# Sheet1.net
KiCad netlist of a schematic drawn in Altium Designer
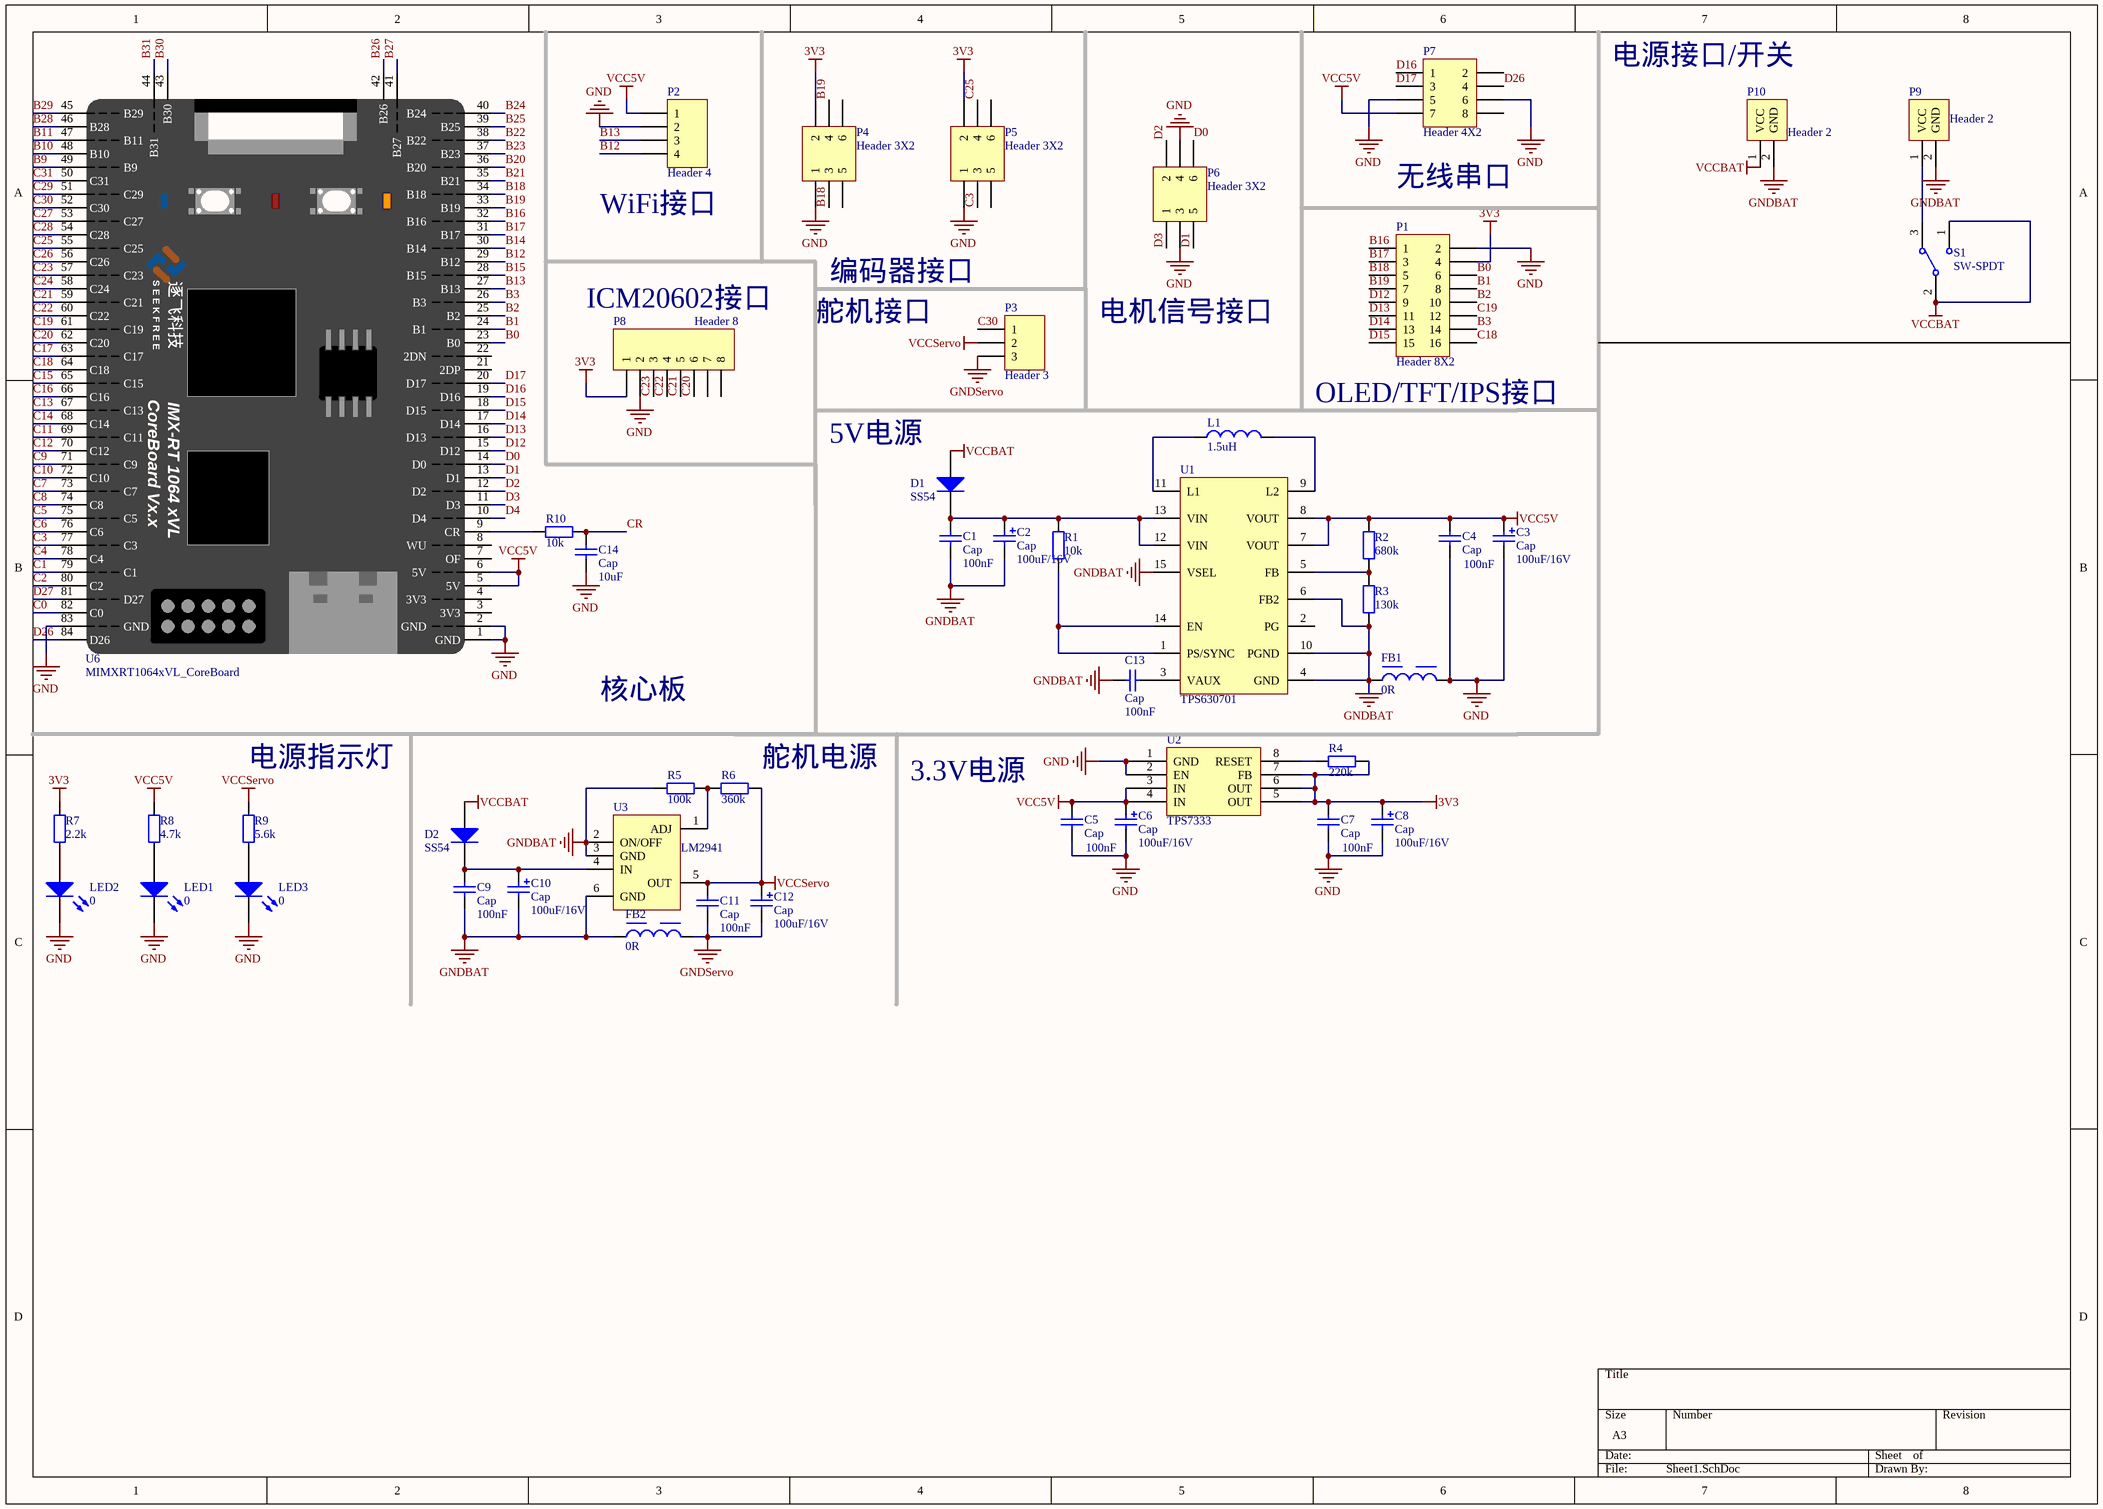
[diagram p0: Sheet1.SchDoc]

(export (version "E")
  (design (tool "Eeschema 10.0.6"))
  (components
    (comp (ref "C1")
      (value "Cap")
      (footprint "0603C")
      (description "Capacitor")
      (fields (field (name "ALTIUM_VALUE") "100nF") (field (name "PUBLISHER") "Altium Limited"))
      (libsource (lib "Schlib1") (part "Cap"))
    )
    (comp (ref "C2")
      (value "Cap")
      (description "Capacitor")
      (fields (field (name "ALTIUM_VALUE") "100uF/16V") (field (name "PUBLISHER") "Altium Limited"))
      (libsource (lib "Schlib1") (part "Cap2"))
    )
    (comp (ref "C3")
      (value "Cap")
      (description "Capacitor")
      (fields (field (name "ALTIUM_VALUE") "100uF/16V") (field (name "PUBLISHER") "Altium Limited"))
      (libsource (lib "Schlib1") (part "Cap2"))
    )
    (comp (ref "C4")
      (value "Cap")
      (footprint "0603C")
      (description "Capacitor")
      (fields (field (name "ALTIUM_VALUE") "100nF") (field (name "PUBLISHER") "Altium Limited"))
      (libsource (lib "Schlib1") (part "Cap"))
    )
    (comp (ref "C5")
      (value "Cap")
      (footprint "0603C")
      (description "Capacitor")
      (fields (field (name "ALTIUM_VALUE") "100nF") (field (name "PUBLISHER") "Altium Limited"))
      (libsource (lib "Schlib1") (part "Cap"))
    )
    (comp (ref "C6")
      (value "Cap")
      (description "Capacitor")
      (fields (field (name "ALTIUM_VALUE") "100uF/16V") (field (name "PUBLISHER") "Altium Limited"))
      (libsource (lib "Schlib1") (part "Cap2"))
    )
    (comp (ref "C7")
      (value "Cap")
      (footprint "0603C")
      (description "Capacitor")
      (fields (field (name "ALTIUM_VALUE") "100nF") (field (name "PUBLISHER") "Altium Limited"))
      (libsource (lib "Schlib1") (part "Cap"))
    )
    (comp (ref "C8")
      (value "Cap")
      (description "Capacitor")
      (fields (field (name "ALTIUM_VALUE") "100uF/16V") (field (name "PUBLISHER") "Altium Limited"))
      (libsource (lib "Schlib1") (part "Cap2"))
    )
    (comp (ref "C9")
      (value "Cap")
      (footprint "0603C")
      (description "Capacitor")
      (fields (field (name "ALTIUM_VALUE") "100nF") (field (name "PUBLISHER") "Altium Limited"))
      (libsource (lib "Schlib1") (part "Cap"))
    )
    (comp (ref "C10")
      (value "Cap")
      (description "Capacitor")
      (fields (field (name "ALTIUM_VALUE") "100uF/16V") (field (name "PUBLISHER") "Altium Limited"))
      (libsource (lib "Schlib1") (part "Cap2"))
    )
    (comp (ref "C11")
      (value "Cap")
      (footprint "0603C")
      (description "Capacitor")
      (fields (field (name "ALTIUM_VALUE") "100nF") (field (name "PUBLISHER") "Altium Limited"))
      (libsource (lib "Schlib1") (part "Cap"))
    )
    (comp (ref "C12")
      (value "Cap")
      (description "Capacitor")
      (fields (field (name "ALTIUM_VALUE") "100uF/16V") (field (name "PUBLISHER") "Altium Limited"))
      (libsource (lib "Schlib1") (part "Cap2"))
    )
    (comp (ref "C13")
      (value "Cap")
      (footprint "0603C")
      (description "Capacitor")
      (fields (field (name "ALTIUM_VALUE") "100nF") (field (name "PUBLISHER") "Altium Limited"))
      (libsource (lib "Schlib1") (part "Cap"))
    )
    (comp (ref "C14")
      (value "Cap")
      (footprint "0603C")
      (description "Capacitor")
      (fields (field (name "ALTIUM_VALUE") "10uF") (field (name "PUBLISHER") "Altium Limited"))
      (libsource (lib "Schlib1") (part "Cap"))
    )
    (comp (ref "D1")
      (value "SS54")
      (footprint "ss54")
      (description "Default Diode")
      (fields (field (name "PUBLISHER") "Altium Limited"))
      (libsource (lib "Schlib1") (part "Diode_1"))
    )
    (comp (ref "D2")
      (value "SS54")
      (footprint "ss54")
      (description "Default Diode")
      (fields (field (name "PUBLISHER") "Altium Limited"))
      (libsource (lib "Schlib1") (part "Diode_1"))
    )
    (comp (ref "FB1")
      (value "0R")
      (footprint "0805")
      (description "Inductor")
      (fields (field (name "PUBLISHER") "Altium Limited"))
      (libsource (lib "Schlib1") (part "FB"))
    )
    (comp (ref "FB2")
      (value "0R")
      (footprint "0805")
      (description "Inductor")
      (fields (field (name "PUBLISHER") "Altium Limited"))
      (libsource (lib "Schlib1") (part "FB"))
    )
    (comp (ref "L1")
      (value "1.5uH")
      (footprint "4R7")
      (description "Inductor")
      (fields (field (name "PUBLISHER") "Altium Limited"))
      (libsource (lib "Schlib1") (part "Inductor_2"))
    )
    (comp (ref "LED1")
      (value "0")
      (footprint "0603C")
      (description "Typical RED, GREEN, YELLOW, AMBER GaAs LED")
      (fields (field (name "PUBLISHER") "Altium Limited"))
      (libsource (lib "Schlib1") (part "LED2"))
    )
    (comp (ref "LED2")
      (value "0")
      (footprint "0603C")
      (description "Typical RED, GREEN, YELLOW, AMBER GaAs LED")
      (fields (field (name "PUBLISHER") "Altium Limited"))
      (libsource (lib "Schlib1") (part "LED2"))
    )
    (comp (ref "LED3")
      (value "0")
      (footprint "0603C")
      (description "Typical RED, GREEN, YELLOW, AMBER GaAs LED")
      (fields (field (name "PUBLISHER") "Altium Limited"))
      (libsource (lib "Schlib1") (part "LED2"))
    )
    (comp (ref "P1")
      (value "Header 8X2")
      (footprint "HDR2X8")
      (description "Header, 8-Pin, Dual row")
      (fields (field (name "PUBLISHER") "Altium Limited"))
      (libsource (lib "Miscellaneous Connectors") (part "Header 8X2"))
    )
    (comp (ref "P2")
      (value "Header 4")
      (footprint "HDR1X4")
      (description "Header, 4-Pin")
      (fields (field (name "PUBLISHER") "Altium Limited"))
      (libsource (lib "Miscellaneous Connectors") (part "Header 4"))
    )
    (comp (ref "P3")
      (value "Header 3")
      (footprint "HDR1X3")
      (description "Header, 3-Pin")
      (fields (field (name "PUBLISHER") "Altium Limited"))
      (libsource (lib "Miscellaneous Connectors") (part "Header 3"))
    )
    (comp (ref "P4")
      (value "Header 3X2")
      (footprint "HDR2X3")
      (description "Header, 3-Pin, Dual row")
      (fields (field (name "PUBLISHER") "Altium Limited"))
      (libsource (lib "Miscellaneous Connectors") (part "Header 3X2"))
    )
    (comp (ref "P5")
      (value "Header 3X2")
      (footprint "HDR2X3")
      (description "Header, 3-Pin, Dual row")
      (fields (field (name "PUBLISHER") "Altium Limited"))
      (libsource (lib "Miscellaneous Connectors") (part "Header 3X2"))
    )
    (comp (ref "P6")
      (value "Header 3X2")
      (footprint "HDR2X3")
      (description "Header, 3-Pin, Dual row")
      (fields (field (name "PUBLISHER") "Altium Limited"))
      (libsource (lib "Miscellaneous Connectors") (part "Header 3X2"))
    )
    (comp (ref "P7")
      (value "Header 4X2")
      (footprint "HDR2X4")
      (description "Header, 4-Pin, Dual row")
      (fields (field (name "PUBLISHER") "Altium Limited"))
      (libsource (lib "Miscellaneous Connectors") (part "Header 4X2"))
    )
    (comp (ref "P8")
      (value "Header 8")
      (footprint "HDR1X8")
      (description "Header, 8-Pin")
      (fields (field (name "PUBLISHER") "Altium Limited"))
      (libsource (lib "Miscellaneous Connectors") (part "Header 8"))
    )
    (comp (ref "P9")
      (value "Header 2")
      (description "Header, 2-Pin")
      (fields (field (name "PUBLISHER") "Altium Limited"))
      (libsource (lib "Schlib1") (part "Header 2_1"))
    )
    (comp (ref "P10")
      (value "Header 2")
      (description "Header, 2-Pin")
      (fields (field (name "PUBLISHER") "Altium Limited"))
      (libsource (lib "Schlib1") (part "Header 2_2"))
    )
    (comp (ref "R1")
      (value "10k")
      (footprint "0603C")
      (description "Resistor")
      (fields (field (name "Comment") "Res2") (field (name "PUBLISHER") "Altium Limited"))
      (libsource (lib "Schlib1") (part "Res2"))
    )
    (comp (ref "R2")
      (value "680k")
      (footprint "0603C")
      (description "Resistor")
      (fields (field (name "Comment") "Res2") (field (name "PUBLISHER") "Altium Limited"))
      (libsource (lib "Schlib1") (part "Res2"))
    )
    (comp (ref "R3")
      (value "130k")
      (footprint "0603C")
      (description "Resistor")
      (fields (field (name "Comment") "Res2") (field (name "PUBLISHER") "Altium Limited"))
      (libsource (lib "Schlib1") (part "Res2"))
    )
    (comp (ref "R4")
      (value "220k")
      (footprint "0603C")
      (description "Resistor")
      (fields (field (name "Comment") "Res2") (field (name "PUBLISHER") "Altium Limited"))
      (libsource (lib "") (part "Res2_1"))
    )
    (comp (ref "R5")
      (value "100k")
      (footprint "0603C")
      (description "Resistor")
      (fields (field (name "Comment") "Res2") (field (name "PUBLISHER") "Altium Limited"))
      (libsource (lib "") (part "Res2_1"))
    )
    (comp (ref "R6")
      (value "360k")
      (footprint "0603C")
      (description "Resistor")
      (fields (field (name "Comment") "Res2") (field (name "PUBLISHER") "Altium Limited"))
      (libsource (lib "") (part "Res2_1"))
    )
    (comp (ref "R7")
      (value "2.2k")
      (footprint "0603C")
      (description "Resistor")
      (fields (field (name "Comment") "Res2") (field (name "PUBLISHER") "Altium Limited"))
      (libsource (lib "Schlib1") (part "Res2"))
    )
    (comp (ref "R8")
      (value "4.7k")
      (footprint "0603C")
      (description "Resistor")
      (fields (field (name "Comment") "Res2") (field (name "PUBLISHER") "Altium Limited"))
      (libsource (lib "Schlib1") (part "Res2"))
    )
    (comp (ref "R9")
      (value "5.6k")
      (footprint "0603C")
      (description "Resistor")
      (fields (field (name "Comment") "Res2") (field (name "PUBLISHER") "Altium Limited"))
      (libsource (lib "Schlib1") (part "Res2"))
    )
    (comp (ref "R10")
      (value "10k")
      (footprint "0603C")
      (description "Resistor")
      (fields (field (name "Comment") "Res2") (field (name "PUBLISHER") "Altium Limited"))
      (libsource (lib "") (part "Res2_1"))
    )
    (comp (ref "S1")
      (value "SW-SPDT")
      (footprint "TL36WW15050")
      (description "SPDT Subminiature Toggle Switch, Right Angle Mounting, Vertical Actuation")
      (fields (field (name "PUBLISHER") "Altium Limited"))
      (libsource (lib "Miscellaneous Devices") (part "SW-SPDT"))
    )
    (comp (ref "U1")
      (value "TPS630701")
      (footprint "HPFC:SO14")
      (libsource (lib "Schlib1") (part "TPS630701"))
    )
    (comp (ref "U2") (value "TPS7333") (footprint "HPFC:SO8") (libsource (lib "Schlib1") (part "TPS7333")))
    (comp (ref "U3")
      (value "LM2941")
      (footprint "HPFC:HDR1X4")
      (description "Header, 4-Pin")
      (fields (field (name "PUBLISHER") "Altium Limited"))
      (libsource (lib "Schlib1") (part "LM2941"))
    )
    (comp (ref "U6")
      (value "MIMXRT1064xVL_CoreBoard")
      (footprint "MIMXRT1064xVL_CoreBoard")
      (description "逐飞科技i.MX RT1064核心板整体原理，可直接使用")
      (libsource (lib "RT1064 V1.2核心板原理库") (part "MIMXRT1064xVL_CoreBoard"))
    )
  )
  (nets
    (net (code "1") (name "/B0") (class "Default")
      (node (ref "P1") (pin "6") (pinfunction "6_6") (pintype "passive"))
      (node (ref "U6") (pin "23") (pinfunction "B0_23") (pintype "passive"))
    )
    (net (code "2") (name "/B1") (class "Default")
      (node (ref "P1") (pin "8") (pinfunction "8_8") (pintype "passive"))
      (node (ref "U6") (pin "24") (pinfunction "B1_24") (pintype "passive"))
    )
    (net (code "3") (name "/B2") (class "Default")
      (node (ref "P1") (pin "10") (pinfunction "10_10") (pintype "passive"))
      (node (ref "U6") (pin "25") (pinfunction "B2_25") (pintype "passive"))
    )
    (net (code "4") (name "/B3") (class "Default")
      (node (ref "P1") (pin "14") (pinfunction "14_14") (pintype "passive"))
      (node (ref "U6") (pin "26") (pinfunction "B3_26") (pintype "passive"))
    )
    (net (code "5") (name "/B9") (class "Default")
      (node (ref "U6") (pin "49") (pinfunction "B9_49") (pintype "passive"))
    )
    (net (code "6") (name "/B10") (class "Default")
      (node (ref "U6") (pin "48") (pinfunction "B10_48") (pintype "passive"))
    )
    (net (code "7") (name "/B11") (class "Default")
      (node (ref "U6") (pin "47") (pinfunction "B11_47") (pintype "passive"))
    )
    (net (code "8") (name "/B12") (class "Default")
      (node (ref "P2") (pin "4") (pinfunction "4_4") (pintype "passive"))
      (node (ref "U6") (pin "29") (pinfunction "B12_29") (pintype "passive"))
    )
    (net (code "9") (name "/B13") (class "Default")
      (node (ref "P2") (pin "3") (pinfunction "3_3") (pintype "passive"))
      (node (ref "U6") (pin "27") (pinfunction "B13_27") (pintype "passive"))
    )
    (net (code "10") (name "/B14") (class "Default")
      (node (ref "U6") (pin "30") (pinfunction "B14_30") (pintype "passive"))
    )
    (net (code "11") (name "/B15") (class "Default")
      (node (ref "U6") (pin "28") (pinfunction "B15_28") (pintype "passive"))
    )
    (net (code "12") (name "/B16") (class "Default")
      (node (ref "P1") (pin "1") (pinfunction "1_1") (pintype "passive"))
      (node (ref "U6") (pin "32") (pinfunction "B16_32") (pintype "passive"))
    )
    (net (code "13") (name "/B17") (class "Default")
      (node (ref "P1") (pin "3") (pinfunction "3_3") (pintype "passive"))
      (node (ref "U6") (pin "31") (pinfunction "B17_31") (pintype "passive"))
    )
    (net (code "14") (name "/B18") (class "Default")
      (node (ref "P1") (pin "5") (pinfunction "5_5") (pintype "passive"))
      (node (ref "P4") (pin "3") (pinfunction "3_3") (pintype "passive"))
      (node (ref "U6") (pin "34") (pinfunction "B18_34") (pintype "passive"))
    )
    (net (code "15") (name "/B19") (class "Default")
      (node (ref "P1") (pin "7") (pinfunction "7_7") (pintype "passive"))
      (node (ref "P4") (pin "4") (pinfunction "4_4") (pintype "passive"))
      (node (ref "U6") (pin "33") (pinfunction "B19_33") (pintype "passive"))
    )
    (net (code "16") (name "/B20") (class "Default")
      (node (ref "U6") (pin "36") (pinfunction "B20_36") (pintype "passive"))
    )
    (net (code "17") (name "/B21") (class "Default")
      (node (ref "U6") (pin "35") (pinfunction "B21_35") (pintype "passive"))
    )
    (net (code "18") (name "/B22") (class "Default")
      (node (ref "U6") (pin "38") (pinfunction "B22_38") (pintype "passive"))
    )
    (net (code "19") (name "/B23") (class "Default")
      (node (ref "U6") (pin "37") (pinfunction "B23_37") (pintype "passive"))
    )
    (net (code "20") (name "/B24") (class "Default")
      (node (ref "U6") (pin "40") (pinfunction "B24_40") (pintype "passive"))
    )
    (net (code "21") (name "/B25") (class "Default")
      (node (ref "U6") (pin "39") (pinfunction "B25_39") (pintype "passive"))
    )
    (net (code "22") (name "/B26") (class "Default")
      (node (ref "U6") (pin "42") (pinfunction "B26_42") (pintype "passive"))
    )
    (net (code "23") (name "/B27") (class "Default")
      (node (ref "U6") (pin "41") (pinfunction "B27_41") (pintype "passive"))
    )
    (net (code "24") (name "/B28") (class "Default")
      (node (ref "U6") (pin "46") (pinfunction "B28_46") (pintype "passive"))
    )
    (net (code "25") (name "/B29") (class "Default")
      (node (ref "U6") (pin "45") (pinfunction "B29_45") (pintype "passive"))
    )
    (net (code "26") (name "/B30") (class "Default")
      (node (ref "U6") (pin "43") (pinfunction "B30_43") (pintype "passive"))
    )
    (net (code "27") (name "/B31") (class "Default")
      (node (ref "U6") (pin "44") (pinfunction "B31_44") (pintype "passive"))
    )
    (net (code "28") (name "/C0") (class "Default")
      (node (ref "U6") (pin "82") (pinfunction "C0_82") (pintype "passive"))
    )
    (net (code "29") (name "/C1") (class "Default")
      (node (ref "U6") (pin "79") (pinfunction "C1_79") (pintype "passive"))
    )
    (net (code "30") (name "/C2") (class "Default")
      (node (ref "U6") (pin "80") (pinfunction "C2_80") (pintype "passive"))
    )
    (net (code "31") (name "/C3") (class "Default")
      (node (ref "P5") (pin "3") (pinfunction "3_3") (pintype "passive"))
      (node (ref "U6") (pin "77") (pinfunction "C3_77") (pintype "passive"))
    )
    (net (code "32") (name "/C4") (class "Default")
      (node (ref "U6") (pin "78") (pinfunction "C4_78") (pintype "passive"))
    )
    (net (code "33") (name "/C5") (class "Default")
      (node (ref "U6") (pin "75") (pinfunction "C5_75") (pintype "passive"))
    )
    (net (code "34") (name "/C6") (class "Default")
      (node (ref "U6") (pin "76") (pinfunction "C6_76") (pintype "passive"))
    )
    (net (code "35") (name "/C7") (class "Default")
      (node (ref "U6") (pin "73") (pinfunction "C7_73") (pintype "passive"))
    )
    (net (code "36") (name "/C8") (class "Default")
      (node (ref "U6") (pin "74") (pinfunction "C8_74") (pintype "passive"))
    )
    (net (code "37") (name "/C9") (class "Default")
      (node (ref "U6") (pin "71") (pinfunction "C9_71") (pintype "passive"))
    )
    (net (code "38") (name "/C10") (class "Default")
      (node (ref "U6") (pin "72") (pinfunction "C10_72") (pintype "passive"))
    )
    (net (code "39") (name "/C11") (class "Default")
      (node (ref "U6") (pin "69") (pinfunction "C11_69") (pintype "passive"))
    )
    (net (code "40") (name "/C12") (class "Default")
      (node (ref "U6") (pin "70") (pinfunction "C12_70") (pintype "passive"))
    )
    (net (code "41") (name "/C13") (class "Default")
      (node (ref "U6") (pin "67") (pinfunction "C13_67") (pintype "passive"))
    )
    (net (code "42") (name "/C14") (class "Default")
      (node (ref "U6") (pin "68") (pinfunction "C14_68") (pintype "passive"))
    )
    (net (code "43") (name "/C15") (class "Default")
      (node (ref "U6") (pin "65") (pinfunction "C15_65") (pintype "passive"))
    )
    (net (code "44") (name "/C16") (class "Default")
      (node (ref "U6") (pin "66") (pinfunction "C16_66") (pintype "passive"))
    )
    (net (code "45") (name "/C17") (class "Default")
      (node (ref "U6") (pin "63") (pinfunction "C17_63") (pintype "passive"))
    )
    (net (code "46") (name "/C18") (class "Default")
      (node (ref "P1") (pin "16") (pinfunction "16_16") (pintype "passive"))
      (node (ref "U6") (pin "64") (pinfunction "C18_64") (pintype "passive"))
    )
    (net (code "47") (name "/C19") (class "Default")
      (node (ref "P1") (pin "12") (pinfunction "12_12") (pintype "passive"))
      (node (ref "U6") (pin "61") (pinfunction "C19_61") (pintype "passive"))
    )
    (net (code "48") (name "/C20") (class "Default")
      (node (ref "P8") (pin "6") (pinfunction "6_6") (pintype "passive"))
      (node (ref "U6") (pin "62") (pinfunction "C20_62") (pintype "passive"))
    )
    (net (code "49") (name "/C21") (class "Default")
      (node (ref "P8") (pin "5") (pinfunction "5_5") (pintype "passive"))
      (node (ref "U6") (pin "59") (pinfunction "C21_59") (pintype "passive"))
    )
    (net (code "50") (name "/C22") (class "Default")
      (node (ref "P8") (pin "4") (pinfunction "4_4") (pintype "passive"))
      (node (ref "U6") (pin "60") (pinfunction "C22_60") (pintype "passive"))
    )
    (net (code "51") (name "/C23") (class "Default")
      (node (ref "P8") (pin "3") (pinfunction "3_3") (pintype "passive"))
      (node (ref "U6") (pin "57") (pinfunction "C23_57") (pintype "passive"))
    )
    (net (code "52") (name "/C24") (class "Default")
      (node (ref "U6") (pin "58") (pinfunction "C24_58") (pintype "passive"))
    )
    (net (code "53") (name "/C25") (class "Default")
      (node (ref "P5") (pin "4") (pinfunction "4_4") (pintype "passive"))
      (node (ref "U6") (pin "55") (pinfunction "C25_55") (pintype "passive"))
    )
    (net (code "54") (name "/C26") (class "Default")
      (node (ref "U6") (pin "56") (pinfunction "C26_56") (pintype "passive"))
    )
    (net (code "55") (name "/C27") (class "Default")
      (node (ref "U6") (pin "53") (pinfunction "C27_53") (pintype "passive"))
    )
    (net (code "56") (name "/C28") (class "Default")
      (node (ref "U6") (pin "54") (pinfunction "C28_54") (pintype "passive"))
    )
    (net (code "57") (name "/C29") (class "Default")
      (node (ref "U6") (pin "51") (pinfunction "C29_51") (pintype "passive"))
    )
    (net (code "58") (name "/C30") (class "Default")
      (node (ref "P3") (pin "1") (pinfunction "1_1") (pintype "passive"))
      (node (ref "U6") (pin "52") (pinfunction "C30_52") (pintype "passive"))
    )
    (net (code "59") (name "/C31") (class "Default")
      (node (ref "U6") (pin "50") (pinfunction "C31_50") (pintype "passive"))
    )
    (net (code "60") (name "/CR") (class "Default")
      (node (ref "C14") (pin "2") (pinfunction "2_2") (pintype "passive"))
      (node (ref "R10") (pin "2") (pinfunction "2_2") (pintype "passive"))
    )
    (net (code "61") (name "/D0") (class "Default")
      (node (ref "P6") (pin "6") (pinfunction "6_6") (pintype "passive"))
      (node (ref "U6") (pin "14") (pinfunction "D0_14") (pintype "passive"))
    )
    (net (code "62") (name "/D1") (class "Default")
      (node (ref "P6") (pin "5") (pinfunction "5_5") (pintype "passive"))
      (node (ref "U6") (pin "13") (pinfunction "D1_13") (pintype "passive"))
    )
    (net (code "63") (name "/D2") (class "Default")
      (node (ref "P6") (pin "2") (pinfunction "2_2") (pintype "passive"))
      (node (ref "U6") (pin "12") (pinfunction "D2_12") (pintype "passive"))
    )
    (net (code "64") (name "/D3") (class "Default")
      (node (ref "P6") (pin "1") (pinfunction "1_1") (pintype "passive"))
      (node (ref "U6") (pin "11") (pinfunction "D3_11") (pintype "passive"))
    )
    (net (code "65") (name "/D4") (class "Default")
      (node (ref "U6") (pin "10") (pinfunction "D4_10") (pintype "passive"))
    )
    (net (code "66") (name "/D12") (class "Default")
      (node (ref "P1") (pin "9") (pinfunction "9_9") (pintype "passive"))
      (node (ref "U6") (pin "15") (pinfunction "D12_15") (pintype "passive"))
    )
    (net (code "67") (name "/D13") (class "Default")
      (node (ref "P1") (pin "11") (pinfunction "11_11") (pintype "passive"))
      (node (ref "U6") (pin "16") (pinfunction "D13_16") (pintype "passive"))
    )
    (net (code "68") (name "/D14") (class "Default")
      (node (ref "P1") (pin "13") (pinfunction "13_13") (pintype "passive"))
      (node (ref "U6") (pin "17") (pinfunction "D14_17") (pintype "passive"))
    )
    (net (code "69") (name "/D15") (class "Default")
      (node (ref "P1") (pin "15") (pinfunction "15_15") (pintype "passive"))
      (node (ref "U6") (pin "18") (pinfunction "D15_18") (pintype "passive"))
    )
    (net (code "70") (name "/D16") (class "Default")
      (node (ref "P7") (pin "1") (pinfunction "1_1") (pintype "passive"))
      (node (ref "U6") (pin "19") (pinfunction "D16_19") (pintype "passive"))
    )
    (net (code "71") (name "/D17") (class "Default")
      (node (ref "P7") (pin "3") (pinfunction "3_3") (pintype "passive"))
      (node (ref "U6") (pin "20") (pinfunction "D17_20") (pintype "passive"))
    )
    (net (code "72") (name "/D26") (class "Default")
      (node (ref "P7") (pin "4") (pinfunction "4_4") (pintype "passive"))
      (node (ref "U6") (pin "84") (pinfunction "D26_84") (pintype "passive"))
    )
    (net (code "73") (name "/D27") (class "Default")
      (node (ref "U6") (pin "81") (pinfunction "D27_81") (pintype "passive"))
    )
    (net (code "74") (name "3V3") (class "Default")
      (node (ref "C7") (pin "2") (pinfunction "2_2") (pintype "passive"))
      (node (ref "C8") (pin "1") (pinfunction "1_1") (pintype "passive"))
      (node (ref "P1") (pin "4") (pinfunction "4_4") (pintype "passive"))
      (node (ref "P4") (pin "2") (pinfunction "2_2") (pintype "passive"))
      (node (ref "P5") (pin "2") (pinfunction "2_2") (pintype "passive"))
      (node (ref "P8") (pin "1") (pinfunction "1_1") (pintype "passive"))
      (node (ref "R4") (pin "2") (pinfunction "2_2") (pintype "passive"))
      (node (ref "R7") (pin "2") (pinfunction "2_2") (pintype "passive"))
      (node (ref "U2") (pin "5") (pinfunction "OUT_5") (pintype "passive"))
      (node (ref "U2") (pin "6") (pinfunction "OUT_6") (pintype "passive"))
      (node (ref "U2") (pin "7") (pinfunction "FB_7") (pintype "passive"))
    )
    (net (code "75") (name "GND") (class "Default")
      (node (ref "C14") (pin "1") (pinfunction "1_1") (pintype "passive"))
      (node (ref "C3") (pin "2") (pinfunction "2_2") (pintype "passive"))
      (node (ref "C4") (pin "1") (pinfunction "1_1") (pintype "passive"))
      (node (ref "C5") (pin "1") (pinfunction "1_1") (pintype "passive"))
      (node (ref "C6") (pin "2") (pinfunction "2_2") (pintype "passive"))
      (node (ref "C7") (pin "1") (pinfunction "1_1") (pintype "passive"))
      (node (ref "C8") (pin "2") (pinfunction "2_2") (pintype "passive"))
      (node (ref "FB1") (pin "2") (pinfunction "2_2") (pintype "passive"))
      (node (ref "LED1") (pin "2") (pinfunction "K_2") (pintype "passive"))
      (node (ref "LED2") (pin "2") (pinfunction "K_2") (pintype "passive"))
      (node (ref "LED3") (pin "2") (pinfunction "K_2") (pintype "passive"))
      (node (ref "P1") (pin "2") (pinfunction "2_2") (pintype "passive"))
      (node (ref "P2") (pin "2") (pinfunction "2_2") (pintype "passive"))
      (node (ref "P4") (pin "1") (pinfunction "1_1") (pintype "passive"))
      (node (ref "P5") (pin "1") (pinfunction "1_1") (pintype "passive"))
      (node (ref "P6") (pin "3") (pinfunction "3_3") (pintype "passive"))
      (node (ref "P6") (pin "4") (pinfunction "4_4") (pintype "passive"))
      (node (ref "P7") (pin "5") (pinfunction "5_5") (pintype "passive"))
      (node (ref "P7") (pin "6") (pinfunction "6_6") (pintype "passive"))
      (node (ref "P8") (pin "2") (pinfunction "2_2") (pintype "passive"))
      (node (ref "U2") (pin "1") (pinfunction "GND_1") (pintype "passive"))
      (node (ref "U2") (pin "2") (pinfunction "EN_2") (pintype "passive"))
      (node (ref "U6") (pin "1") (pinfunction "GND_1") (pintype "passive"))
      (node (ref "U6") (pin "2") (pinfunction "GND_2") (pintype "passive"))
      (node (ref "U6") (pin "83") (pinfunction "GND_83") (pintype "passive"))
    )
    (net (code "76") (name "GNDBAT") (class "Default")
      (node (ref "C1") (pin "1") (pinfunction "1_1") (pintype "passive"))
      (node (ref "C10") (pin "2") (pinfunction "2_2") (pintype "passive"))
      (node (ref "C13") (pin "2") (pinfunction "2_2") (pintype "passive"))
      (node (ref "C2") (pin "2") (pinfunction "2_2") (pintype "passive"))
      (node (ref "C9") (pin "1") (pinfunction "1_1") (pintype "passive"))
      (node (ref "FB1") (pin "1") (pinfunction "1_1") (pintype "passive"))
      (node (ref "FB2") (pin "1") (pinfunction "1_1") (pintype "passive"))
      (node (ref "P10") (pin "2") (pinfunction "GND_2") (pintype "passive"))
      (node (ref "P9") (pin "2") (pinfunction "GND_2") (pintype "passive"))
      (node (ref "R3") (pin "1") (pinfunction "1_1") (pintype "passive"))
      (node (ref "R5") (pin "1") (pinfunction "1_1") (pintype "passive"))
      (node (ref "U1") (pin "10") (pinfunction "PGND_10") (pintype "passive"))
      (node (ref "U1") (pin "15") (pinfunction "VSEL_15") (pintype "passive"))
      (node (ref "U1") (pin "4") (pinfunction "GND_4") (pintype "passive"))
      (node (ref "U1") (pin "6") (pinfunction "FB2_6") (pintype "passive"))
      (node (ref "U3") (pin "2") (pinfunction "ON/OFF_2") (pintype "passive"))
      (node (ref "U3") (pin "3") (pinfunction "GND_3") (pintype "passive"))
      (node (ref "U3") (pin "6") (pinfunction "GND_6") (pintype "passive"))
    )
    (net (code "77") (name "GNDServo") (class "Default")
      (node (ref "C11") (pin "1") (pinfunction "1_1") (pintype "passive"))
      (node (ref "C12") (pin "2") (pinfunction "2_2") (pintype "passive"))
      (node (ref "FB2") (pin "2") (pinfunction "2_2") (pintype "passive"))
      (node (ref "P3") (pin "3") (pinfunction "3_3") (pintype "passive"))
    )
    (net (code "78") (name "Net-(D1-K)") (class "Default")
      (node (ref "C1") (pin "2") (pinfunction "2_2") (pintype "passive"))
      (node (ref "C2") (pin "1") (pinfunction "1_1") (pintype "passive"))
      (node (ref "D1") (pin "2") (pinfunction "K_2") (pintype "passive"))
      (node (ref "R1") (pin "2") (pinfunction "2_2") (pintype "passive"))
      (node (ref "U1") (pin "12") (pinfunction "VIN_12") (pintype "passive"))
      (node (ref "U1") (pin "13") (pinfunction "VIN_13") (pintype "passive"))
    )
    (net (code "79") (name "Net-(D2-K)") (class "Default")
      (node (ref "C10") (pin "1") (pinfunction "1_1") (pintype "passive"))
      (node (ref "C9") (pin "2") (pinfunction "2_2") (pintype "passive"))
      (node (ref "D2") (pin "2") (pinfunction "K_2") (pintype "passive"))
      (node (ref "U3") (pin "4") (pinfunction "IN_4") (pintype "passive"))
    )
    (net (code "80") (name "Net-(LED1-A)") (class "Default")
      (node (ref "LED1") (pin "1") (pinfunction "A_1") (pintype "passive"))
      (node (ref "R8") (pin "1") (pinfunction "1_1") (pintype "passive"))
    )
    (net (code "81") (name "Net-(LED2-A)") (class "Default")
      (node (ref "LED2") (pin "1") (pinfunction "A_1") (pintype "passive"))
      (node (ref "R7") (pin "1") (pinfunction "1_1") (pintype "passive"))
    )
    (net (code "82") (name "Net-(LED3-A)") (class "Default")
      (node (ref "LED3") (pin "1") (pinfunction "A_1") (pintype "passive"))
      (node (ref "R9") (pin "1") (pinfunction "1_1") (pintype "passive"))
    )
    (net (code "83") (name "Net-(P9-VCC)") (class "Default")
      (node (ref "P9") (pin "1") (pinfunction "VCC_1") (pintype "passive"))
      (node (ref "S1") (pin "3") (pinfunction "3_3") (pintype "passive"))
    )
    (net (code "84") (name "Net-(U1-EN)") (class "Default")
      (node (ref "R1") (pin "1") (pinfunction "1_1") (pintype "passive"))
      (node (ref "U1") (pin "1") (pinfunction "PS/SYNC_1") (pintype "passive"))
      (node (ref "U1") (pin "14") (pinfunction "EN_14") (pintype "passive"))
    )
    (net (code "85") (name "Net-(U1-FB)") (class "Default")
      (node (ref "R2") (pin "1") (pinfunction "1_1") (pintype "passive"))
      (node (ref "R3") (pin "2") (pinfunction "2_2") (pintype "passive"))
      (node (ref "U1") (pin "5") (pinfunction "FB_5") (pintype "passive"))
    )
    (net (code "86") (name "Net-(U1-L1)") (class "Default")
      (node (ref "L1") (pin "1") (pinfunction "1_1") (pintype "passive"))
      (node (ref "U1") (pin "11") (pinfunction "L1_11") (pintype "passive"))
    )
    (net (code "87") (name "Net-(U1-L2)") (class "Default")
      (node (ref "L1") (pin "2") (pinfunction "2_2") (pintype "passive"))
      (node (ref "U1") (pin "9") (pinfunction "L2_9") (pintype "passive"))
    )
    (net (code "88") (name "Net-(U1-VAUX)") (class "Default")
      (node (ref "C13") (pin "1") (pinfunction "1_1") (pintype "passive"))
      (node (ref "U1") (pin "3") (pinfunction "VAUX_3") (pintype "passive"))
    )
    (net (code "89") (name "Net-(U2-RESET)") (class "Default")
      (node (ref "R4") (pin "1") (pinfunction "1_1") (pintype "passive"))
      (node (ref "U2") (pin "8") (pinfunction "RESET_8") (pintype "passive"))
    )
    (net (code "90") (name "Net-(U3-ADJ)") (class "Default")
      (node (ref "R5") (pin "2") (pinfunction "2_2") (pintype "passive"))
      (node (ref "R6") (pin "1") (pinfunction "1_1") (pintype "passive"))
      (node (ref "U3") (pin "1") (pinfunction "ADJ_1") (pintype "passive"))
    )
    (net (code "91") (name "Net-(U6-CR)") (class "Default")
      (node (ref "R10") (pin "1") (pinfunction "1_1") (pintype "passive"))
      (node (ref "U6") (pin "9") (pinfunction "CR_9") (pintype "passive"))
    )
    (net (code "92") (name "VCC5V") (class "Default")
      (node (ref "C3") (pin "1") (pinfunction "1_1") (pintype "passive"))
      (node (ref "C4") (pin "2") (pinfunction "2_2") (pintype "passive"))
      (node (ref "C5") (pin "2") (pinfunction "2_2") (pintype "passive"))
      (node (ref "C6") (pin "1") (pinfunction "1_1") (pintype "passive"))
      (node (ref "P2") (pin "1") (pinfunction "1_1") (pintype "passive"))
      (node (ref "P7") (pin "7") (pinfunction "7_7") (pintype "passive"))
      (node (ref "R2") (pin "2") (pinfunction "2_2") (pintype "passive"))
      (node (ref "R8") (pin "2") (pinfunction "2_2") (pintype "passive"))
      (node (ref "U1") (pin "7") (pinfunction "VOUT_7") (pintype "passive"))
      (node (ref "U1") (pin "8") (pinfunction "VOUT_8") (pintype "passive"))
      (node (ref "U2") (pin "3") (pinfunction "IN_3") (pintype "passive"))
      (node (ref "U2") (pin "4") (pinfunction "IN_4") (pintype "passive"))
      (node (ref "U6") (pin "5") (pinfunction "5V_5") (pintype "passive"))
      (node (ref "U6") (pin "6") (pinfunction "5V_6") (pintype "passive"))
    )
    (net (code "93") (name "VCCBAT") (class "Default")
      (node (ref "D1") (pin "1") (pinfunction "A_1") (pintype "passive"))
      (node (ref "D2") (pin "1") (pinfunction "A_1") (pintype "passive"))
      (node (ref "P10") (pin "1") (pinfunction "VCC_1") (pintype "passive"))
      (node (ref "S1") (pin "1") (pinfunction "1_1") (pintype "passive"))
      (node (ref "S1") (pin "2") (pinfunction "2_2") (pintype "passive"))
    )
    (net (code "94") (name "VCCServo") (class "Default")
      (node (ref "C11") (pin "2") (pinfunction "2_2") (pintype "passive"))
      (node (ref "C12") (pin "1") (pinfunction "1_1") (pintype "passive"))
      (node (ref "P3") (pin "2") (pinfunction "2_2") (pintype "passive"))
      (node (ref "R6") (pin "2") (pinfunction "2_2") (pintype "passive"))
      (node (ref "R9") (pin "2") (pinfunction "2_2") (pintype "passive"))
      (node (ref "U3") (pin "5") (pinfunction "OUT_5") (pintype "passive"))
    )
    (net (code "95") (name "unconnected-(P4-Pad5)") (class "Default")
      (node (ref "P4") (pin "5") (pinfunction "5_5") (pintype "passive"))
    )
    (net (code "96") (name "unconnected-(P4-Pad6)") (class "Default")
      (node (ref "P4") (pin "6") (pinfunction "6_6") (pintype "passive"))
    )
    (net (code "97") (name "unconnected-(P5-Pad5)") (class "Default")
      (node (ref "P5") (pin "5") (pinfunction "5_5") (pintype "passive"))
    )
    (net (code "98") (name "unconnected-(P5-Pad6)") (class "Default")
      (node (ref "P5") (pin "6") (pinfunction "6_6") (pintype "passive"))
    )
    (net (code "99") (name "unconnected-(P7-Pad2)") (class "Default")
      (node (ref "P7") (pin "2") (pinfunction "2_2") (pintype "passive"))
    )
    (net (code "100") (name "unconnected-(P7-Pad8)") (class "Default")
      (node (ref "P7") (pin "8") (pinfunction "8_8") (pintype "passive"))
    )
    (net (code "101") (name "unconnected-(P8-Pad7)") (class "Default")
      (node (ref "P8") (pin "7") (pinfunction "7_7") (pintype "passive"))
    )
    (net (code "102") (name "unconnected-(P8-Pad8)") (class "Default")
      (node (ref "P8") (pin "8") (pinfunction "8_8") (pintype "passive"))
    )
    (net (code "103") (name "unconnected-(U1-PG-Pad2)") (class "Default")
      (node (ref "U1") (pin "2") (pinfunction "PG_2") (pintype "passive"))
    )
    (net (code "104") (name "unconnected-(U6-2DN-Pad22)") (class "Default")
      (node (ref "U6") (pin "22") (pinfunction "2DN_22") (pintype "passive"))
    )
    (net (code "105") (name "unconnected-(U6-2DP-Pad21)") (class "Default")
      (node (ref "U6") (pin "21") (pinfunction "2DP_21") (pintype "passive"))
    )
    (net (code "106") (name "unconnected-(U6-3V3-Pad3)") (class "Default")
      (node (ref "U6") (pin "3") (pinfunction "3V3_3") (pintype "passive"))
    )
    (net (code "107") (name "unconnected-(U6-3V3-Pad4)") (class "Default")
      (node (ref "U6") (pin "4") (pinfunction "3V3_4") (pintype "passive"))
    )
    (net (code "108") (name "unconnected-(U6-OF-Pad7)") (class "Default")
      (node (ref "U6") (pin "7") (pinfunction "OF_7") (pintype "passive"))
    )
    (net (code "109") (name "unconnected-(U6-WU-Pad8)") (class "Default")
      (node (ref "U6") (pin "8") (pinfunction "WU_8") (pintype "passive"))
    )
  )
)
